# takahoot-bumper.net
KiCad netlist of a schematic drawn in EAGLE
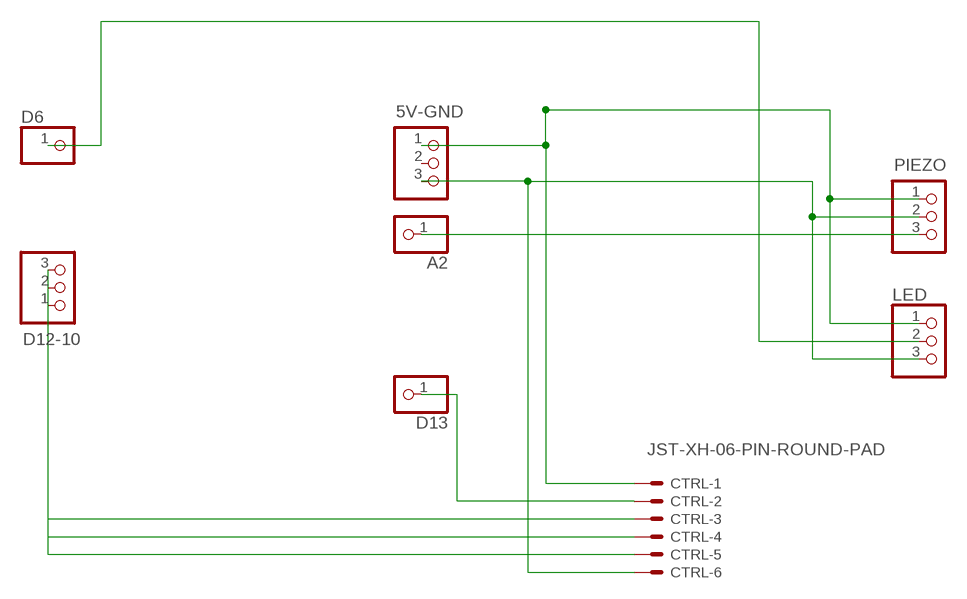
[diagram p0: schematic, sheet 1]

(export (version "E")
  (design (tool "Eeschema 10.0.6"))
  (components
    (comp (ref "5V-GND")
      (value "PINHD-1X3")
      (footprint "eagle-import:1X03")
      (libsource (lib "eagle-import") (part "PINHD-1X3"))
    )
    (comp (ref "A2")
      (value "PINHD-1X1")
      (footprint "eagle-import:1X01")
      (libsource (lib "eagle-import") (part "PINHD-1X1"))
    )
    (comp (ref "CTRL")
      (value "JST-XH-06-PIN-ROUND-PAD")
      (footprint "eagle-import:JST-XH-06-PACKAGE-ROUND-PAD")
      (libsource (lib "eagle-import") (part "JST-XH-06-PIN-ROUND-PAD"))
    )
    (comp (ref "D6")
      (value "PINHD-1X1")
      (footprint "eagle-import:1X01")
      (libsource (lib "eagle-import") (part "PINHD-1X1"))
    )
    (comp (ref "D12-10")
      (value "PINHD-1X3")
      (footprint "eagle-import:1X03")
      (libsource (lib "eagle-import") (part "PINHD-1X3"))
    )
    (comp (ref "D13")
      (value "PINHD-1X1")
      (footprint "eagle-import:1X01")
      (libsource (lib "eagle-import") (part "PINHD-1X1"))
    )
    (comp (ref "LED")
      (value "PINHD-1X3/90")
      (footprint "eagle-import:1X03_90")
      (libsource (lib "eagle-import") (part "PINHD-1X3/90"))
    )
    (comp (ref "PIEZO")
      (value "PINHD-1X3/90")
      (footprint "eagle-import:1X03_90")
      (libsource (lib "eagle-import") (part "PINHD-1X3/90"))
    )
  )
  (nets
    (net (code "1") (name "Net-(A2-Pad1)") (class "Default")
      (node (ref "A2") (pin "1") (pinfunction "1_1") (pintype "passive"))
      (node (ref "PIEZO") (pin "3") (pinfunction "3_3") (pintype "passive"))
    )
    (net (code "2") (name "Net-(CTRLA-S)") (class "Default")
      (node (ref "5V-GND") (pin "1") (pinfunction "1_1") (pintype "passive"))
      (node (ref "CTRL") (pin "1") (pinfunction "S_1") (pintype "passive"))
      (node (ref "LED") (pin "1") (pinfunction "1_1") (pintype "passive"))
      (node (ref "PIEZO") (pin "1") (pinfunction "1_1") (pintype "passive"))
    )
    (net (code "3") (name "Net-(CTRLB-S)") (class "Default")
      (node (ref "CTRL") (pin "2") (pinfunction "S_2") (pintype "passive"))
      (node (ref "D13") (pin "1") (pinfunction "1_1") (pintype "passive"))
    )
    (net (code "4") (name "Net-(CTRLC-S)") (class "Default")
      (node (ref "CTRL") (pin "3") (pinfunction "S_3") (pintype "passive"))
      (node (ref "D12-10") (pin "3") (pinfunction "3_3") (pintype "passive"))
    )
    (net (code "5") (name "Net-(CTRLD-S)") (class "Default")
      (node (ref "CTRL") (pin "4") (pinfunction "S_4") (pintype "passive"))
      (node (ref "D12-10") (pin "2") (pinfunction "2_2") (pintype "passive"))
    )
    (net (code "6") (name "Net-(CTRLE-S)") (class "Default")
      (node (ref "CTRL") (pin "5") (pinfunction "S_5") (pintype "passive"))
      (node (ref "D12-10") (pin "1") (pinfunction "1_1") (pintype "passive"))
    )
    (net (code "7") (name "Net-(CTRLF-S)") (class "Default")
      (node (ref "5V-GND") (pin "3") (pinfunction "3_3") (pintype "passive"))
      (node (ref "CTRL") (pin "6") (pinfunction "S_6") (pintype "passive"))
      (node (ref "LED") (pin "3") (pinfunction "3_3") (pintype "passive"))
      (node (ref "PIEZO") (pin "2") (pinfunction "2_2") (pintype "passive"))
    )
    (net (code "8") (name "Net-(D6-Pad1)") (class "Default")
      (node (ref "D6") (pin "1") (pinfunction "1_1") (pintype "passive"))
      (node (ref "LED") (pin "2") (pinfunction "2_2") (pintype "passive"))
    )
    (net (code "9") (name "unconnected-(5V-GND-Pad2)") (class "Default")
      (node (ref "5V-GND") (pin "2") (pinfunction "2_2") (pintype "passive"))
    )
  )
)
